# boosterpack.net
KiCad netlist of a schematic drawn in EAGLE
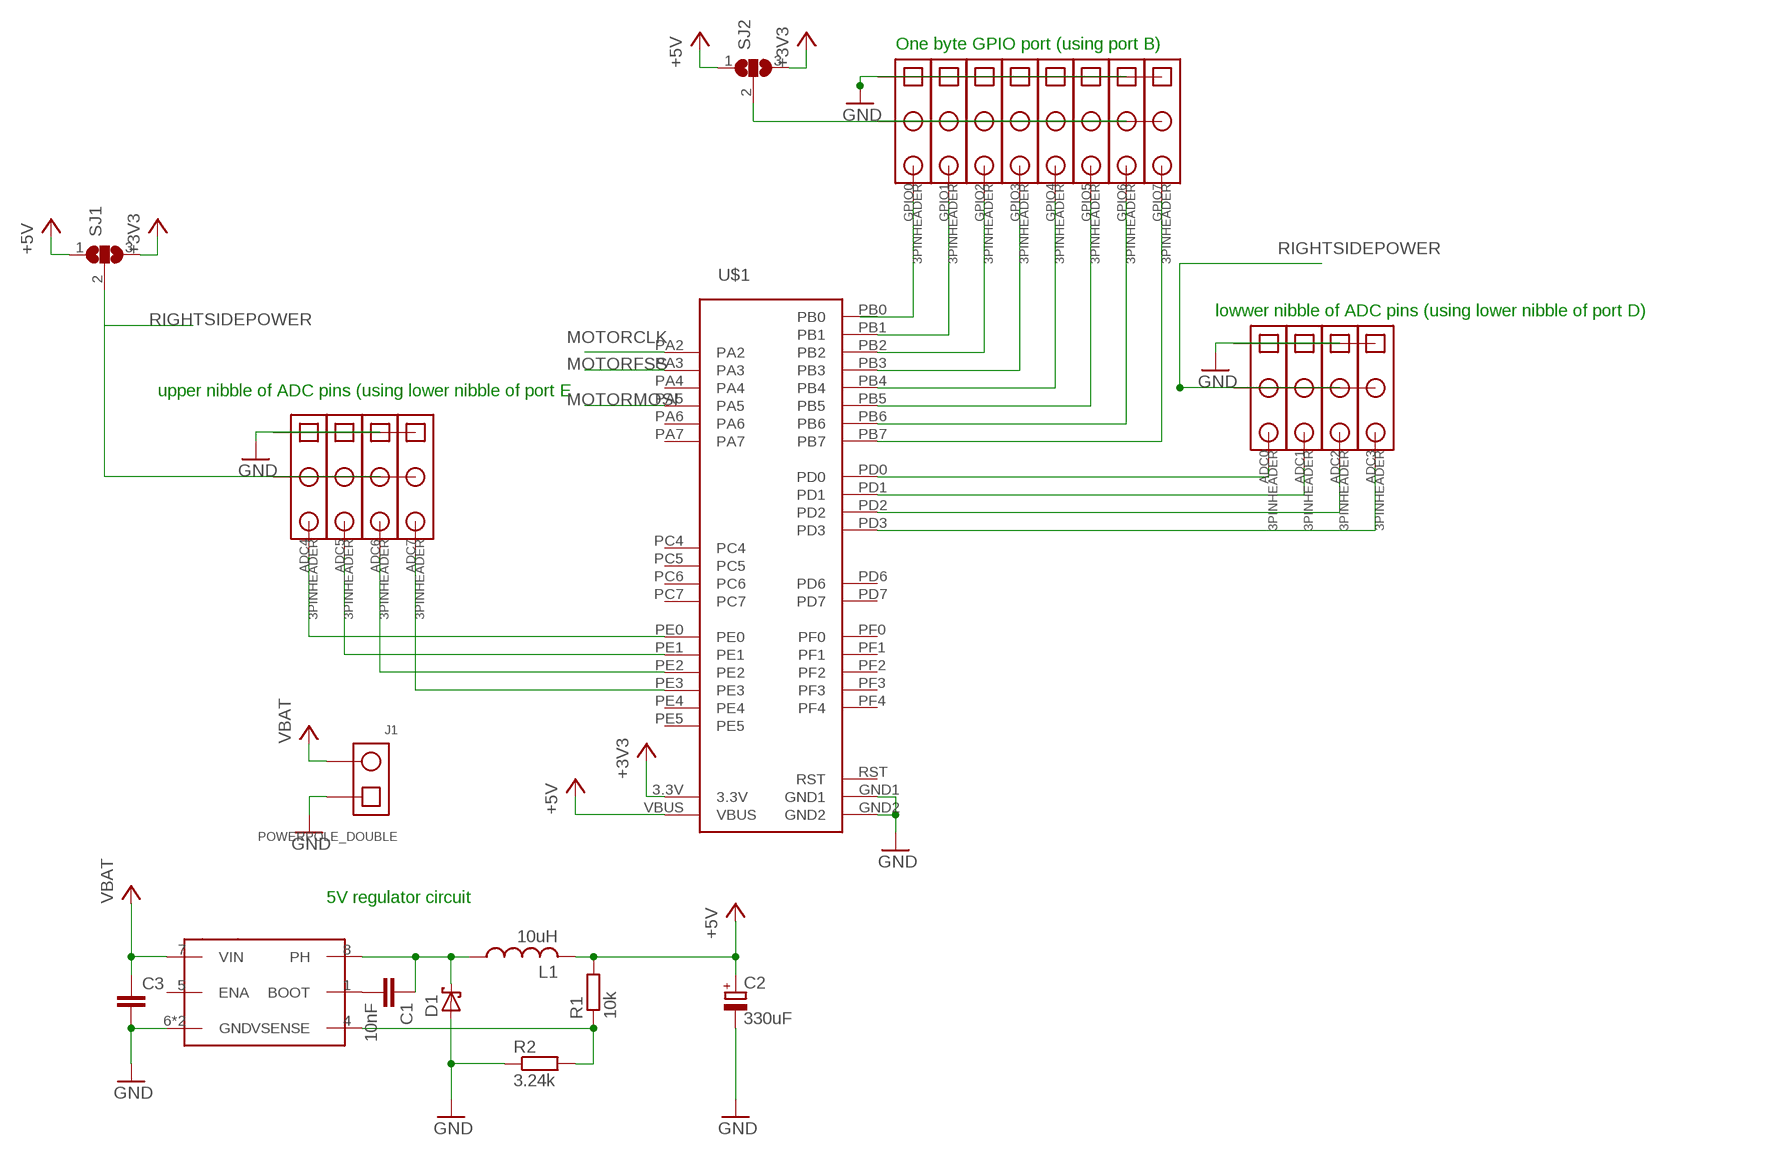
[diagram p0: schematic, sheet 1]

(export (version "E")
  (design (tool "Eeschema 10.0.6"))
  (components
    (comp (ref "ADC0")
      (value "3PINHEADER")
      (footprint "eagle-import:3PINHEADER")
      (libsource (lib "eagle-import") (part "3PINHEADER"))
    )
    (comp (ref "ADC1")
      (value "3PINHEADER")
      (footprint "eagle-import:3PINHEADER")
      (libsource (lib "eagle-import") (part "3PINHEADER"))
    )
    (comp (ref "ADC2")
      (value "3PINHEADER")
      (footprint "eagle-import:3PINHEADER")
      (libsource (lib "eagle-import") (part "3PINHEADER"))
    )
    (comp (ref "ADC3")
      (value "3PINHEADER")
      (footprint "eagle-import:3PINHEADER")
      (libsource (lib "eagle-import") (part "3PINHEADER"))
    )
    (comp (ref "ADC4")
      (value "3PINHEADER")
      (footprint "eagle-import:3PINHEADER")
      (libsource (lib "eagle-import") (part "3PINHEADER"))
    )
    (comp (ref "ADC5")
      (value "3PINHEADER")
      (footprint "eagle-import:3PINHEADER")
      (libsource (lib "eagle-import") (part "3PINHEADER"))
    )
    (comp (ref "ADC6")
      (value "3PINHEADER")
      (footprint "eagle-import:3PINHEADER")
      (libsource (lib "eagle-import") (part "3PINHEADER"))
    )
    (comp (ref "ADC7")
      (value "3PINHEADER")
      (footprint "eagle-import:3PINHEADER")
      (libsource (lib "eagle-import") (part "3PINHEADER"))
    )
    (comp (ref "C1")
      (value "10nF")
      (footprint "eagle-import:C025-024X044")
      (libsource (lib "eagle-import") (part "C-EU025-024X044"))
    )
    (comp (ref "C2")
      (value "330uF")
      (footprint "eagle-import:B45181A")
      (libsource (lib "eagle-import") (part "CPOL-EUB45181A"))
    )
    (comp (ref "C3")
      (value "C-EU025-024X044")
      (footprint "eagle-import:C025-024X044")
      (libsource (lib "eagle-import") (part "C-EU025-024X044"))
    )
    (comp (ref "D1")
      (value "SCHOTTKY-DIODEDO35-7")
      (footprint "eagle-import:DO35-7")
      (libsource (lib "eagle-import") (part "SCHOTTKY-DIODEDO35-7"))
    )
    (comp (ref "GPIO0")
      (value "3PINHEADER")
      (footprint "eagle-import:3PINHEADER")
      (libsource (lib "eagle-import") (part "3PINHEADER"))
    )
    (comp (ref "GPIO1")
      (value "3PINHEADER")
      (footprint "eagle-import:3PINHEADER")
      (libsource (lib "eagle-import") (part "3PINHEADER"))
    )
    (comp (ref "GPIO2")
      (value "3PINHEADER")
      (footprint "eagle-import:3PINHEADER")
      (libsource (lib "eagle-import") (part "3PINHEADER"))
    )
    (comp (ref "GPIO3")
      (value "3PINHEADER")
      (footprint "eagle-import:3PINHEADER")
      (libsource (lib "eagle-import") (part "3PINHEADER"))
    )
    (comp (ref "GPIO4")
      (value "3PINHEADER")
      (footprint "eagle-import:3PINHEADER")
      (libsource (lib "eagle-import") (part "3PINHEADER"))
    )
    (comp (ref "GPIO5")
      (value "3PINHEADER")
      (footprint "eagle-import:3PINHEADER")
      (libsource (lib "eagle-import") (part "3PINHEADER"))
    )
    (comp (ref "GPIO6")
      (value "3PINHEADER")
      (footprint "eagle-import:3PINHEADER")
      (libsource (lib "eagle-import") (part "3PINHEADER"))
    )
    (comp (ref "GPIO7")
      (value "3PINHEADER")
      (footprint "eagle-import:3PINHEADER")
      (libsource (lib "eagle-import") (part "3PINHEADER"))
    )
    (comp (ref "J1")
      (value "POWERPOLE_DOUBLE")
      (footprint "eagle-import:POWERPOLE_DOUBLE")
      (libsource (lib "eagle-import") (part "POWERPOLE_DOUBLE"))
    )
    (comp (ref "L1")
      (value "10uH")
      (footprint "eagle-import:SDR1006")
      (libsource (lib "eagle-import") (part "SDR1006"))
    )
    (comp (ref "R1")
      (value "10k")
      (footprint "eagle-import:0204_5")
      (libsource (lib "eagle-import") (part "R-EU_0204/5"))
    )
    (comp (ref "R2")
      (value "3.24k")
      (footprint "eagle-import:0204_5")
      (libsource (lib "eagle-import") (part "R-EU_0204/5"))
    )
    (comp (ref "SJ1")
      (value "SJ2W")
      (footprint "eagle-import:SJ_2")
      (libsource (lib "eagle-import") (part "SJ2W"))
    )
    (comp (ref "SJ2")
      (value "SJ2W")
      (footprint "eagle-import:SJ_2")
      (libsource (lib "eagle-import") (part "SJ2W"))
    )
    (comp (ref "U$1")
      (value "STELLARIS-LAUNCHPADSTELLARIS-LAUNCHPAD-XL")
      (footprint "eagle-import:LAUNCHPAD-XL")
      (libsource (lib "eagle-import") (part "STELLARIS-LAUNCHPADSTELLARIS-LAUNCHPAD-XL"))
    )
    (comp (ref "U$2")
      (value "TPS5450")
      (footprint "eagle-import:DDS")
      (libsource (lib "eagle-import") (part "TPS5450"))
    )
  )
  (nets
    (net (code "1") (name "+3V3") (class "Default")
      (node (ref "SJ1") (pin "3") (pinfunction "3_3") (pintype "passive"))
      (node (ref "SJ2") (pin "3") (pinfunction "3_3") (pintype "passive"))
      (node (ref "U$1") (pin "3.3V") (pinfunction "3.3V_3.3V") (pintype "power_in"))
    )
    (net (code "2") (name "+5V") (class "Default")
      (node (ref "C2") (pin "+") (pinfunction "+_+") (pintype "passive"))
      (node (ref "L1") (pin "P$2") (pinfunction "2_P$2") (pintype "passive"))
      (node (ref "R1") (pin "2") (pinfunction "2_2") (pintype "passive"))
      (node (ref "SJ1") (pin "1") (pinfunction "1_1") (pintype "passive"))
      (node (ref "SJ2") (pin "1") (pinfunction "1_1") (pintype "passive"))
      (node (ref "U$1") (pin "VBUS") (pinfunction "VBUS_VBUS") (pintype "power_in"))
    )
    (net (code "3") (name "/MOTORCLK") (class "Default")
      (node (ref "U$1") (pin "PA2") (pinfunction "PA2_PA2") (pintype "bidirectional"))
    )
    (net (code "4") (name "/MOTORFSS") (class "Default")
      (node (ref "U$1") (pin "PA3") (pinfunction "PA3_PA3") (pintype "bidirectional"))
    )
    (net (code "5") (name "/MOTORMOSI") (class "Default")
      (node (ref "U$1") (pin "PA5") (pinfunction "PA5_PA5") (pintype "bidirectional"))
    )
    (net (code "6") (name "/RIGHTSIDEPOWER") (class "Default")
      (node (ref "ADC0") (pin "2") (pinfunction "2_2") (pintype "bidirectional"))
      (node (ref "ADC1") (pin "2") (pinfunction "2_2") (pintype "bidirectional"))
      (node (ref "ADC2") (pin "2") (pinfunction "2_2") (pintype "bidirectional"))
      (node (ref "ADC3") (pin "2") (pinfunction "2_2") (pintype "bidirectional"))
      (node (ref "ADC4") (pin "2") (pinfunction "2_2") (pintype "bidirectional"))
      (node (ref "ADC5") (pin "2") (pinfunction "2_2") (pintype "bidirectional"))
      (node (ref "ADC6") (pin "2") (pinfunction "2_2") (pintype "bidirectional"))
      (node (ref "ADC7") (pin "2") (pinfunction "2_2") (pintype "bidirectional"))
      (node (ref "SJ1") (pin "2") (pinfunction "2_2") (pintype "passive"))
    )
    (net (code "7") (name "/RST") (class "Default")
      (node (ref "U$1") (pin "RST") (pinfunction "RST_RST") (pintype "power_in"))
    )
    (net (code "8") (name "GND") (class "Default")
      (node (ref "ADC0") (pin "1") (pinfunction "1_1") (pintype "bidirectional"))
      (node (ref "ADC1") (pin "1") (pinfunction "1_1") (pintype "bidirectional"))
      (node (ref "ADC2") (pin "1") (pinfunction "1_1") (pintype "bidirectional"))
      (node (ref "ADC3") (pin "1") (pinfunction "1_1") (pintype "bidirectional"))
      (node (ref "ADC4") (pin "1") (pinfunction "1_1") (pintype "bidirectional"))
      (node (ref "ADC5") (pin "1") (pinfunction "1_1") (pintype "bidirectional"))
      (node (ref "ADC6") (pin "1") (pinfunction "1_1") (pintype "bidirectional"))
      (node (ref "ADC7") (pin "1") (pinfunction "1_1") (pintype "bidirectional"))
      (node (ref "C2") (pin "-") (pinfunction "-_-") (pintype "passive"))
      (node (ref "C3") (pin "2") (pinfunction "2_2") (pintype "passive"))
      (node (ref "D1") (pin "A") (pinfunction "A_A") (pintype "passive"))
      (node (ref "GPIO0") (pin "1") (pinfunction "1_1") (pintype "bidirectional"))
      (node (ref "GPIO1") (pin "1") (pinfunction "1_1") (pintype "bidirectional"))
      (node (ref "GPIO2") (pin "1") (pinfunction "1_1") (pintype "bidirectional"))
      (node (ref "GPIO3") (pin "1") (pinfunction "1_1") (pintype "bidirectional"))
      (node (ref "GPIO4") (pin "1") (pinfunction "1_1") (pintype "bidirectional"))
      (node (ref "GPIO5") (pin "1") (pinfunction "1_1") (pintype "bidirectional"))
      (node (ref "GPIO6") (pin "1") (pinfunction "1_1") (pintype "bidirectional"))
      (node (ref "GPIO7") (pin "1") (pinfunction "1_1") (pintype "bidirectional"))
      (node (ref "J1") (pin "1") (pinfunction "1_1") (pintype "bidirectional"))
      (node (ref "R2") (pin "1") (pinfunction "1_1") (pintype "passive"))
      (node (ref "U$1") (pin "GND1") (pinfunction "GND1_GND1") (pintype "bidirectional"))
      (node (ref "U$1") (pin "GND2") (pinfunction "GND2_GND2") (pintype "power_in"))
      (node (ref "U$2") (pin "6") (pinfunction "GND_6") (pintype "bidirectional"))
      (node (ref "U$2") (pin "GROUNDPAD") (pinfunction "GND_GROUNDPAD") (pintype "bidirectional"))
    )
    (net (code "9") (name "Net-(ADC0-Pad3)") (class "Default")
      (node (ref "ADC0") (pin "3") (pinfunction "3_3") (pintype "bidirectional"))
      (node (ref "U$1") (pin "PD0") (pinfunction "PD0_PD0") (pintype "bidirectional"))
    )
    (net (code "10") (name "Net-(ADC1-Pad3)") (class "Default")
      (node (ref "ADC1") (pin "3") (pinfunction "3_3") (pintype "bidirectional"))
      (node (ref "U$1") (pin "PD1") (pinfunction "PD1_PD1") (pintype "bidirectional"))
    )
    (net (code "11") (name "Net-(ADC2-Pad3)") (class "Default")
      (node (ref "ADC2") (pin "3") (pinfunction "3_3") (pintype "bidirectional"))
      (node (ref "U$1") (pin "PD2") (pinfunction "PD2_PD2") (pintype "bidirectional"))
    )
    (net (code "12") (name "Net-(ADC3-Pad3)") (class "Default")
      (node (ref "ADC3") (pin "3") (pinfunction "3_3") (pintype "bidirectional"))
      (node (ref "U$1") (pin "PD3") (pinfunction "PD3_PD3") (pintype "bidirectional"))
    )
    (net (code "13") (name "Net-(ADC4-Pad3)") (class "Default")
      (node (ref "ADC4") (pin "3") (pinfunction "3_3") (pintype "bidirectional"))
      (node (ref "U$1") (pin "PE0") (pinfunction "PE0_PE0") (pintype "bidirectional"))
    )
    (net (code "14") (name "Net-(ADC5-Pad3)") (class "Default")
      (node (ref "ADC5") (pin "3") (pinfunction "3_3") (pintype "bidirectional"))
      (node (ref "U$1") (pin "PE1") (pinfunction "PE1_PE1") (pintype "bidirectional"))
    )
    (net (code "15") (name "Net-(ADC6-Pad3)") (class "Default")
      (node (ref "ADC6") (pin "3") (pinfunction "3_3") (pintype "bidirectional"))
      (node (ref "U$1") (pin "PE2") (pinfunction "PE2_PE2") (pintype "bidirectional"))
    )
    (net (code "16") (name "Net-(ADC7-Pad3)") (class "Default")
      (node (ref "ADC7") (pin "3") (pinfunction "3_3") (pintype "bidirectional"))
      (node (ref "U$1") (pin "PE3") (pinfunction "PE3_PE3") (pintype "bidirectional"))
    )
    (net (code "17") (name "Net-(GPIO0-Pad2)") (class "Default")
      (node (ref "GPIO0") (pin "2") (pinfunction "2_2") (pintype "bidirectional"))
      (node (ref "GPIO1") (pin "2") (pinfunction "2_2") (pintype "bidirectional"))
      (node (ref "GPIO2") (pin "2") (pinfunction "2_2") (pintype "bidirectional"))
      (node (ref "GPIO3") (pin "2") (pinfunction "2_2") (pintype "bidirectional"))
      (node (ref "GPIO4") (pin "2") (pinfunction "2_2") (pintype "bidirectional"))
      (node (ref "GPIO5") (pin "2") (pinfunction "2_2") (pintype "bidirectional"))
      (node (ref "GPIO6") (pin "2") (pinfunction "2_2") (pintype "bidirectional"))
      (node (ref "GPIO7") (pin "2") (pinfunction "2_2") (pintype "bidirectional"))
      (node (ref "SJ2") (pin "2") (pinfunction "2_2") (pintype "passive"))
    )
    (net (code "18") (name "Net-(GPIO0-Pad3)") (class "Default")
      (node (ref "GPIO0") (pin "3") (pinfunction "3_3") (pintype "bidirectional"))
      (node (ref "U$1") (pin "PB0") (pinfunction "PB0_PB0") (pintype "bidirectional"))
    )
    (net (code "19") (name "Net-(GPIO1-Pad3)") (class "Default")
      (node (ref "GPIO1") (pin "3") (pinfunction "3_3") (pintype "bidirectional"))
      (node (ref "U$1") (pin "PB1") (pinfunction "PB1_PB1") (pintype "bidirectional"))
    )
    (net (code "20") (name "Net-(GPIO2-Pad3)") (class "Default")
      (node (ref "GPIO2") (pin "3") (pinfunction "3_3") (pintype "bidirectional"))
      (node (ref "U$1") (pin "PB2") (pinfunction "PB2_PB2") (pintype "bidirectional"))
    )
    (net (code "21") (name "Net-(GPIO3-Pad3)") (class "Default")
      (node (ref "GPIO3") (pin "3") (pinfunction "3_3") (pintype "bidirectional"))
      (node (ref "U$1") (pin "PB3") (pinfunction "PB3_PB3") (pintype "bidirectional"))
    )
    (net (code "22") (name "Net-(GPIO4-Pad3)") (class "Default")
      (node (ref "GPIO4") (pin "3") (pinfunction "3_3") (pintype "bidirectional"))
      (node (ref "U$1") (pin "PB4") (pinfunction "PB4_PB4") (pintype "bidirectional"))
    )
    (net (code "23") (name "Net-(GPIO5-Pad3)") (class "Default")
      (node (ref "GPIO5") (pin "3") (pinfunction "3_3") (pintype "bidirectional"))
      (node (ref "U$1") (pin "PB5") (pinfunction "PB5_PB5") (pintype "bidirectional"))
    )
    (net (code "24") (name "Net-(GPIO6-Pad3)") (class "Default")
      (node (ref "GPIO6") (pin "3") (pinfunction "3_3") (pintype "bidirectional"))
      (node (ref "U$1") (pin "PB6") (pinfunction "PB6_PB6") (pintype "bidirectional"))
    )
    (net (code "25") (name "Net-(GPIO7-Pad3)") (class "Default")
      (node (ref "GPIO7") (pin "3") (pinfunction "3_3") (pintype "bidirectional"))
      (node (ref "U$1") (pin "PB7") (pinfunction "PB7_PB7") (pintype "bidirectional"))
    )
    (net (code "26") (name "Net-(L1-1)") (class "Default")
      (node (ref "C1") (pin "1") (pinfunction "1_1") (pintype "passive"))
      (node (ref "D1") (pin "C") (pinfunction "C_C") (pintype "passive"))
      (node (ref "L1") (pin "P$1") (pinfunction "1_P$1") (pintype "passive"))
      (node (ref "U$2") (pin "8") (pinfunction "PH_8") (pintype "bidirectional"))
    )
    (net (code "27") (name "Net-(U$2-BOOT)") (class "Default")
      (node (ref "C1") (pin "2") (pinfunction "2_2") (pintype "passive"))
      (node (ref "U$2") (pin "1") (pinfunction "BOOT_1") (pintype "bidirectional"))
    )
    (net (code "28") (name "Net-(U$2-VSENSE)") (class "Default")
      (node (ref "R1") (pin "1") (pinfunction "1_1") (pintype "passive"))
      (node (ref "R2") (pin "2") (pinfunction "2_2") (pintype "passive"))
      (node (ref "U$2") (pin "4") (pinfunction "VSENSE_4") (pintype "bidirectional"))
    )
    (net (code "29") (name "VBAT") (class "Default")
      (node (ref "C3") (pin "1") (pinfunction "1_1") (pintype "passive"))
      (node (ref "J1") (pin "2") (pinfunction "2_2") (pintype "bidirectional"))
      (node (ref "U$2") (pin "7") (pinfunction "VIN_7") (pintype "bidirectional"))
    )
    (net (code "30") (name "unconnected-(U$1-PadPA4)") (class "Default")
      (node (ref "U$1") (pin "PA4") (pinfunction "PA4_PA4") (pintype "bidirectional"))
    )
    (net (code "31") (name "unconnected-(U$1-PadPA6)") (class "Default")
      (node (ref "U$1") (pin "PA6") (pinfunction "PA6_PA6") (pintype "bidirectional"))
    )
    (net (code "32") (name "unconnected-(U$1-PadPA7)") (class "Default")
      (node (ref "U$1") (pin "PA7") (pinfunction "PA7_PA7") (pintype "bidirectional"))
    )
    (net (code "33") (name "unconnected-(U$1-PadPC4)") (class "Default")
      (node (ref "U$1") (pin "PC4") (pinfunction "PC4_PC4") (pintype "bidirectional"))
    )
    (net (code "34") (name "unconnected-(U$1-PadPC5)") (class "Default")
      (node (ref "U$1") (pin "PC5") (pinfunction "PC5_PC5") (pintype "bidirectional"))
    )
    (net (code "35") (name "unconnected-(U$1-PadPC6)") (class "Default")
      (node (ref "U$1") (pin "PC6") (pinfunction "PC6_PC6") (pintype "bidirectional"))
    )
    (net (code "36") (name "unconnected-(U$1-PadPC7)") (class "Default")
      (node (ref "U$1") (pin "PC7") (pinfunction "PC7_PC7") (pintype "bidirectional"))
    )
    (net (code "37") (name "unconnected-(U$1-PadPD6)") (class "Default")
      (node (ref "U$1") (pin "PD6") (pinfunction "PD6_PD6") (pintype "bidirectional"))
    )
    (net (code "38") (name "unconnected-(U$1-PadPD7)") (class "Default")
      (node (ref "U$1") (pin "PD7") (pinfunction "PD7_PD7") (pintype "bidirectional"))
    )
    (net (code "39") (name "unconnected-(U$1-PadPE4)") (class "Default")
      (node (ref "U$1") (pin "PE4") (pinfunction "PE4_PE4") (pintype "bidirectional"))
    )
    (net (code "40") (name "unconnected-(U$1-PadPE5)") (class "Default")
      (node (ref "U$1") (pin "PE5") (pinfunction "PE5_PE5") (pintype "bidirectional"))
    )
    (net (code "41") (name "unconnected-(U$1-PadPF0)") (class "Default")
      (node (ref "U$1") (pin "PF0") (pinfunction "PF0_PF0") (pintype "bidirectional"))
    )
    (net (code "42") (name "unconnected-(U$1-PadPF1)") (class "Default")
      (node (ref "U$1") (pin "PF1") (pinfunction "PF1_PF1") (pintype "bidirectional"))
    )
    (net (code "43") (name "unconnected-(U$1-PadPF2)") (class "Default")
      (node (ref "U$1") (pin "PF2") (pinfunction "PF2_PF2") (pintype "bidirectional"))
    )
    (net (code "44") (name "unconnected-(U$1-PadPF3)") (class "Default")
      (node (ref "U$1") (pin "PF3") (pinfunction "PF3_PF3") (pintype "bidirectional"))
    )
    (net (code "45") (name "unconnected-(U$1-PadPF4)") (class "Default")
      (node (ref "U$1") (pin "PF4") (pinfunction "PF4_PF4") (pintype "bidirectional"))
    )
    (net (code "46") (name "unconnected-(U$2-ENA-Pad5)") (class "Default")
      (node (ref "U$2") (pin "5") (pinfunction "ENA_5") (pintype "bidirectional"))
    )
  )
)
